# Power.net
KiCad netlist of a schematic drawn in Altium Designer
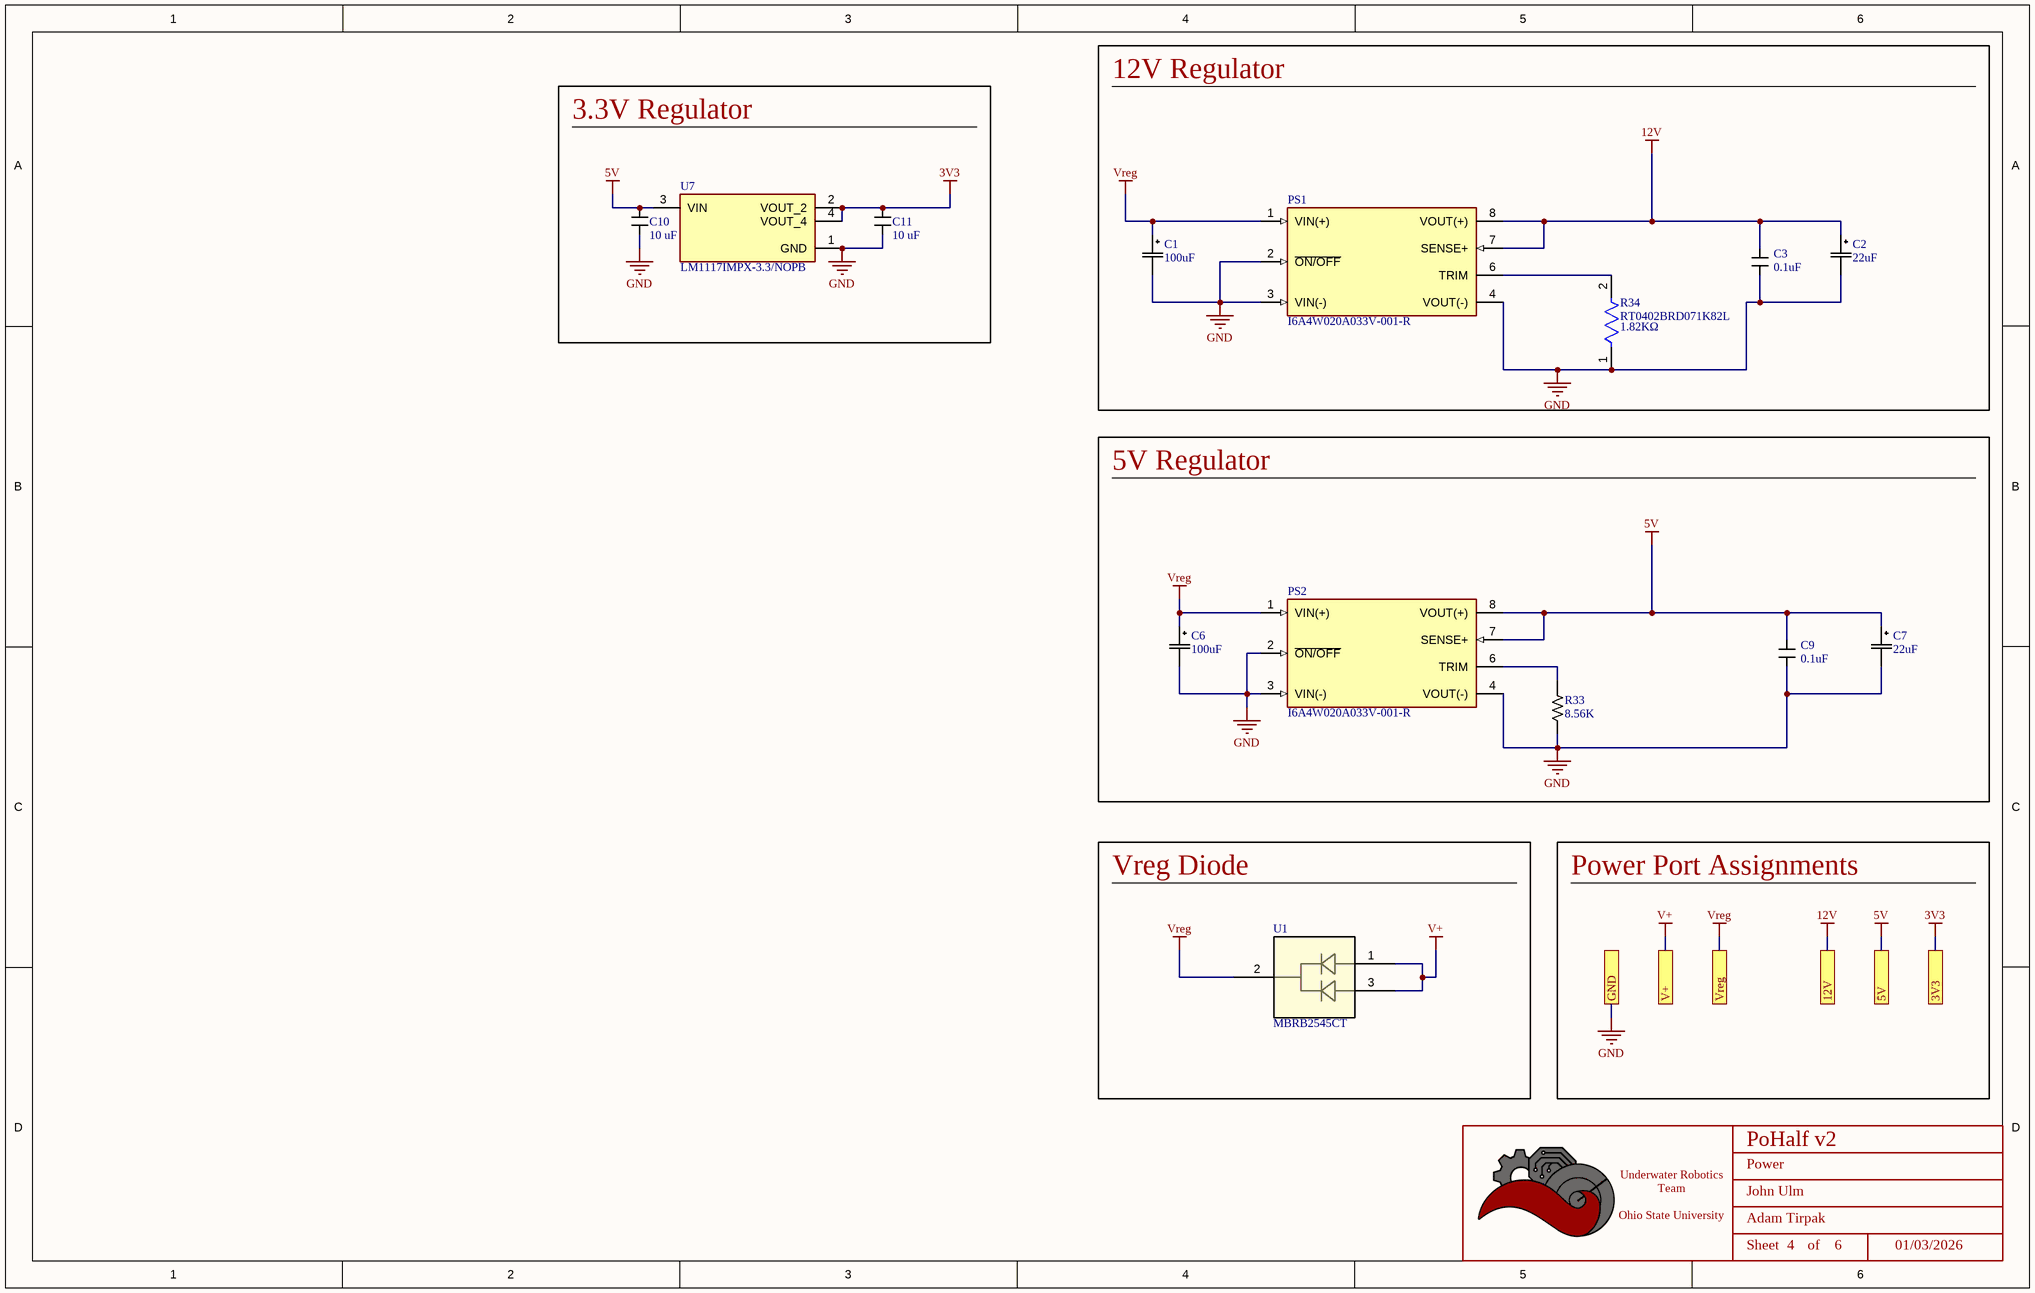
[diagram p0: Power.SchDoc]

(export (version "E")
  (design (tool "Eeschema 10.0.6"))
  (components
    (comp (ref "C1")
      (value "100uF")
      (footprint "PCAP_8x5.4-ELECT_NCA")
      (description "100 µF 35 V Aluminum Electrolytic Capacitors Radial, Can - SMD 1000 Hrs")
      (fields
        (field (name "MANUFACTURER_PART_NUMBER") "UCB1V0R1MCL1GS")
        (field (name "Comment") "100uF electrolytic 35 V")
        (field (name "COPYRIGHT") "Copyright (C) 2022 Ultra Librarian. All rights reserved.")
        (field (name "MADE BY") "Tyson Nguyen")
      )
      (libsource (lib "Capacitors") (part "CAP ALUM 100UF 20% 35V SMD"))
    )
    (comp (ref "C2")
      (value "22uF")
      (footprint "PCAP_8x5.4-ELECT_NCA")
      (description "22 µF 35 V Aluminum Electrolytic Capacitors Radial, Can - SMD 1000 Hrs")
      (fields
        (field (name "VOLTAGE") "35V")
        (field (name "Comment") "22uF electrolytic 35 V")
        (field (name "MADE BY") "Robert Pafford")
      )
      (libsource (lib "Capacitors") (part "CAP ALUM 22UF 20% 35V SMD"))
    )
    (comp (ref "C3")
      (value "CL05A104KA5NNNC")
      (footprint "CAPACITOR_0402")
      (description "0.1 µF ±10% 25V Ceramic Capacitor X5R 0402 (1005 Metric)")
      (fields (field (name "CAPACITANCE") "0.1uF") (field (name "TOLERANCE") "+/- 10%"))
      (libsource (lib "Capacitors") (part "CAP CER 0.1UF 25V X5R 0402"))
    )
    (comp (ref "C6")
      (value "100uF")
      (footprint "PCAP_8x5.4-ELECT_NCA")
      (description "100 µF 35 V Aluminum Electrolytic Capacitors Radial, Can - SMD 1000 Hrs")
      (fields
        (field (name "MANUFACTURER_PART_NUMBER") "UCB1V0R1MCL1GS")
        (field (name "Comment") "100uF electrolytic 35 V")
        (field (name "COPYRIGHT") "Copyright (C) 2022 Ultra Librarian. All rights reserved.")
        (field (name "MADE BY") "Tyson Nguyen")
      )
      (libsource (lib "Capacitors") (part "CAP ALUM 100UF 20% 35V SMD"))
    )
    (comp (ref "C7")
      (value "22uF")
      (footprint "PCAP_8x5.4-ELECT_NCA")
      (description "22 µF 35 V Aluminum Electrolytic Capacitors Radial, Can - SMD 1000 Hrs")
      (fields
        (field (name "VOLTAGE") "35V")
        (field (name "Comment") "22uF electrolytic 35 V")
        (field (name "MADE BY") "Robert Pafford")
      )
      (libsource (lib "Capacitors") (part "CAP ALUM 22UF 20% 35V SMD"))
    )
    (comp (ref "C9")
      (value "CL05A104KA5NNNC")
      (footprint "CAPACITOR_0402")
      (description "0.1 µF ±10% 25V Ceramic Capacitor X5R 0402 (1005 Metric)")
      (fields (field (name "CAPACITANCE") "0.1uF") (field (name "TOLERANCE") "+/- 10%"))
      (libsource (lib "Capacitors") (part "CAP CER 0.1UF 25V X5R 0402"))
    )
    (comp (ref "C10")
      (value "10uF Ceramic 6.3V")
      (footprint "CAPACITOR_0603")
      (description "Cap 10uF 6.3V +/-20%\r\nCeramic 0603")
      (fields
        (field (name "TOLERANCE") "+/- 20%")
        (field (name "VOLTAGE") "6.3V")
        (field (name "VALUE (UF)") "10 uF")
        (field (name "MADE BY") "Flip B")
      )
      (libsource (lib "Capacitors") (part "CAPACITOR_10uF_0603"))
    )
    (comp (ref "C11")
      (value "10uF Ceramic 6.3V")
      (footprint "CAPACITOR_0603")
      (description "Cap 10uF 6.3V +/-20%\r\nCeramic 0603")
      (fields
        (field (name "TOLERANCE") "+/- 20%")
        (field (name "VOLTAGE") "6.3V")
        (field (name "VALUE (UF)") "10 uF")
        (field (name "MADE BY") "Flip B")
      )
      (libsource (lib "Capacitors") (part "CAPACITOR_10uF_0603"))
    )
    (comp (ref "PS1")
      (value "I6A4W020A033V-001-R")
      (footprint "CONV_I6A4W020A033V-001-R")
      (description "Non-Isolated PoL Module DC DC Converter 1 Output 3.3 ~ 15V 20A 9V - 53V Input")
      (fields (field (name "MF") "TDK-Lambda Americas"))
      (libsource (lib "I6A4W020A033V-001-R") (part "I6A4W020A033V-001-R"))
    )
    (comp (ref "PS2")
      (value "I6A4W020A033V-001-R")
      (footprint "CONV_I6A4W020A033V-001-R")
      (description "Non-Isolated PoL Module DC DC Converter 1 Output 3.3 ~ 15V 20A 9V - 53V Input")
      (fields (field (name "MF") "TDK-Lambda Americas"))
      (libsource (lib "I6A4W020A033V-001-R") (part "I6A4W020A033V-001-R"))
    )
    (comp (ref "R33")
      (value "RES 8.56K OHM 1% 1/16W 0402")
      (footprint "RESISTOR_0402")
      (fields
        (field (name "TOLERANCE") "+/- 1%")
        (field (name "VALUE (OHMS)") "8.56K")
        (field (name "MADE BY") "John Ulm")
        (field (name "VERIFIED BY") "*")
      )
      (libsource (lib "Resistors") (part "RESISTOR_8.56K_1%_0402"))
    )
    (comp (ref "R34")
      (value "RT0402BRD071K82L")
      (footprint "FP-RT0402-MFG")
      (description "RES SMD 1.82K OHM 0.1% 1/16W")
      (fields
        (field (name "OCTOPART") "https://octopart.com/rt0402brd071k82l-yageo-1433757")
        (field (name "TOLERANCE") "0.001")
        (field (name "RESISTANCE") "1.82KΩ")
      )
      (libsource (lib "Altium Content Vault") (part "1029c3af85768c4190bb7ad29bc67b5"))
    )
    (comp (ref "U1")
      (value "MBRB2545CT")
      (footprint "D2PAK_VIS")
      (description "Diode Array 1 Pair Common Cathode 45 V Surface Mount TO-263-3, D²Pak (2 Leads + Tab), TO-263AB")
      (fields (field (name "COPYRIGHT") "Copyright (C) 2023 Ultra Librarian. All rights reserved."))
      (libsource (lib "Diodes") (part "MBRB2545CT"))
    )
    (comp (ref "U7")
      (value "LM1117IMPX-3.3/NOPB")
      (footprint "SOT-223-4")
      (description "800-mA 15-V linear voltage regulator 4-SOT-223 -40 to 125")
      (fields (field (name "MF") "Texas Instruments"))
      (libsource (lib "Integrated Circuits") (part "LM1117IMPX-3.3/NOPB"))
    )
  )
  (nets
    (net (code "1") (name "3V3") (class "Default")
      (node (ref "C11") (pin "1") (pinfunction "1_1") (pintype "passive"))
      (node (ref "U7") (pin "2") (pinfunction "VOUT_2_2") (pintype "power_in"))
      (node (ref "U7") (pin "4") (pinfunction "VOUT_4_4") (pintype "power_in"))
    )
    (net (code "2") (name "5V") (class "Default")
      (node (ref "C10") (pin "1") (pinfunction "1_1") (pintype "passive"))
      (node (ref "C7") (pin "1") (pinfunction "1_1") (pintype "passive"))
      (node (ref "C9") (pin "1") (pinfunction "1_1") (pintype "passive"))
      (node (ref "PS2") (pin "7") (pinfunction "SENSE+_7") (pintype "input"))
      (node (ref "PS2") (pin "8") (pinfunction "VOUT(+)_8") (pintype "power_in"))
      (node (ref "U7") (pin "3") (pinfunction "VIN_3") (pintype "power_in"))
    )
    (net (code "3") (name "12V") (class "Default")
      (node (ref "C2") (pin "1") (pinfunction "1_1") (pintype "passive"))
      (node (ref "C3") (pin "1") (pinfunction "1_1") (pintype "passive"))
      (node (ref "PS1") (pin "7") (pinfunction "SENSE+_7") (pintype "input"))
      (node (ref "PS1") (pin "8") (pinfunction "VOUT(+)_8") (pintype "power_in"))
    )
    (net (code "4") (name "GND") (class "Default")
      (node (ref "C1") (pin "2") (pinfunction "2_2") (pintype "passive"))
      (node (ref "C10") (pin "2") (pinfunction "2_2") (pintype "passive"))
      (node (ref "C11") (pin "2") (pinfunction "2_2") (pintype "passive"))
      (node (ref "C2") (pin "2") (pinfunction "2_2") (pintype "passive"))
      (node (ref "C3") (pin "2") (pinfunction "2_2") (pintype "passive"))
      (node (ref "C6") (pin "2") (pinfunction "2_2") (pintype "passive"))
      (node (ref "C7") (pin "2") (pinfunction "2_2") (pintype "passive"))
      (node (ref "C9") (pin "2") (pinfunction "2_2") (pintype "passive"))
      (node (ref "PS1") (pin "2") (pinfunction "~{ON/OFF}_2") (pintype "input"))
      (node (ref "PS1") (pin "3") (pinfunction "VIN(-)_3") (pintype "input"))
      (node (ref "PS1") (pin "4") (pinfunction "VOUT(-)_4") (pintype "power_in"))
      (node (ref "PS2") (pin "2") (pinfunction "~{ON/OFF}_2") (pintype "input"))
      (node (ref "PS2") (pin "3") (pinfunction "VIN(-)_3") (pintype "input"))
      (node (ref "PS2") (pin "4") (pinfunction "VOUT(-)_4") (pintype "power_in"))
      (node (ref "R33") (pin "2") (pinfunction "2_2") (pintype "passive"))
      (node (ref "R34") (pin "1") (pinfunction "1_1") (pintype "passive"))
      (node (ref "U7") (pin "1") (pinfunction "GND_1") (pintype "power_in"))
    )
    (net (code "5") (name "Net-(PS1-TRIM)") (class "Default")
      (node (ref "PS1") (pin "6") (pinfunction "TRIM_6") (pintype "passive"))
      (node (ref "R34") (pin "2") (pinfunction "2_2") (pintype "passive"))
    )
    (net (code "6") (name "Net-(PS2-TRIM)") (class "Default")
      (node (ref "PS2") (pin "6") (pinfunction "TRIM_6") (pintype "passive"))
      (node (ref "R33") (pin "1") (pinfunction "1_1") (pintype "passive"))
    )
    (net (code "7") (name "V+") (class "Default")
      (node (ref "U1") (pin "1") (pinfunction "1_1") (pintype "passive"))
      (node (ref "U1") (pin "3") (pinfunction "3_3") (pintype "passive"))
    )
    (net (code "8") (name "Vreg") (class "Default")
      (node (ref "C1") (pin "1") (pinfunction "1_1") (pintype "passive"))
      (node (ref "C6") (pin "1") (pinfunction "1_1") (pintype "passive"))
      (node (ref "PS1") (pin "1") (pinfunction "VIN(+)_1") (pintype "input"))
      (node (ref "PS2") (pin "1") (pinfunction "VIN(+)_1") (pintype "input"))
      (node (ref "U1") (pin "2") (pinfunction "2_2") (pintype "passive"))
    )
  )
)
